# In-Out.net
KiCad netlist of a schematic drawn in Altium Designer
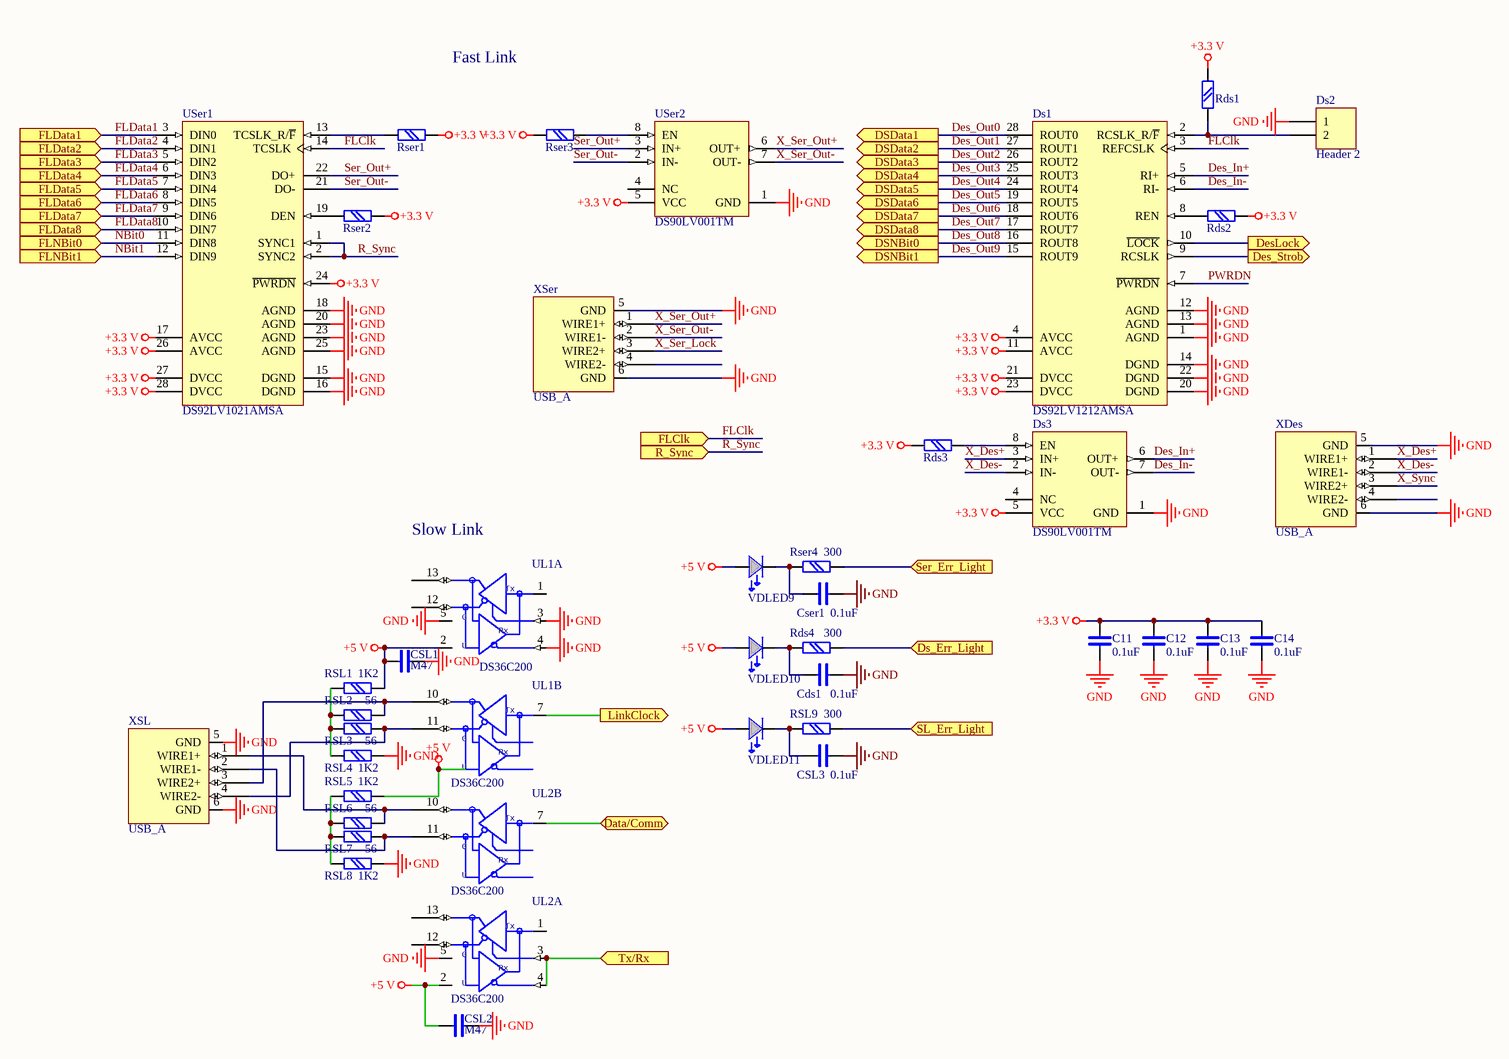
[diagram p0: In-Out.SchDoc]

(export (version "E")
  (design (tool "Eeschema 10.0.6"))
  (components
    (comp (ref "C11") (value "0.1uF") (footprint "chip0805") (libsource (lib "*") (part "C")))
    (comp (ref "C12") (value "0.1uF") (footprint "chip0805") (libsource (lib "*") (part "C")))
    (comp (ref "C13") (value "0.1uF") (footprint "chip0805") (libsource (lib "*") (part "C")))
    (comp (ref "C14") (value "0.1uF") (footprint "chip0805") (libsource (lib "*") (part "C")))
    (comp (ref "Cds1") (value "0.1uF") (footprint "chip0805") (libsource (lib "vDevice") (part "C")))
    (comp (ref "Cser1") (value "0.1uF") (footprint "chip0805") (libsource (lib "vDevice") (part "C")))
    (comp (ref "CSL1") (value "M47") (footprint "chip0805") (libsource (lib "*") (part "C")))
    (comp (ref "CSL2") (value "M47") (footprint "chip0805") (libsource (lib "*") (part "C")))
    (comp (ref "CSL3") (value "0.1uF") (footprint "chip0805") (libsource (lib "vDevice") (part "C")))
    (comp (ref "Ds1")
      (value "DS92LV1212AMSA")
      (footprint "MSA28_N")
      (fields
        (field (name "MANUFACTURER") "National Semiconductor")
        (field (name "PUBLISHER") "Altium Limited")
      )
      (libsource (lib "NSC Interface") (part "DS92LV1212AMSA"))
    )
    (comp (ref "Ds2")
      (value "Header 2")
      (footprint "HDR1X2")
      (description "Header, 2-Pin")
      (fields (field (name "PUBLISHER") "Altium Limited"))
      (libsource (lib "Miscellaneous Connectors") (part "Header 2"))
    )
    (comp (ref "Ds3")
      (value "DS90LV001TM")
      (footprint "M08A_N")
      (description "800 Mbps LVDS Buffer, 8-pin Narrow SOIC")
      (fields
        (field (name "MANUFACTURER") "National Semiconductor")
        (field (name "PUBLISHER") "Altium Limited")
      )
      (libsource (lib "NSC Interface") (part "DS90LV001TM"))
    )
    (comp (ref "Rds1") (value "R") (footprint "chip0805") (libsource (lib "vDevice") (part "R")))
    (comp (ref "Rds2") (value "R") (footprint "chip0805") (libsource (lib "vDevice") (part "R")))
    (comp (ref "Rds3") (value "R") (footprint "chip0805") (libsource (lib "vDevice") (part "R")))
    (comp (ref "Rds4") (value "300") (footprint "chip0805") (libsource (lib "vDevice") (part "R")))
    (comp (ref "Rser1") (value "R") (footprint "chip0805") (libsource (lib "vDevice") (part "R")))
    (comp (ref "Rser2") (value "R") (footprint "chip0805") (libsource (lib "vDevice") (part "R")))
    (comp (ref "Rser3") (value "R") (footprint "chip0805") (libsource (lib "vDevice") (part "R")))
    (comp (ref "Rser4") (value "300") (footprint "chip0805") (libsource (lib "vDevice") (part "R")))
    (comp (ref "RSL1") (value "1K2") (footprint "chip0805") (libsource (lib "*") (part "R")))
    (comp (ref "RSL2") (value "56") (footprint "chip0805") (libsource (lib "*") (part "R")))
    (comp (ref "RSL3") (value "56") (footprint "chip0805") (libsource (lib "*") (part "R")))
    (comp (ref "RSL4") (value "1K2") (footprint "chip0805") (libsource (lib "*") (part "R")))
    (comp (ref "RSL5") (value "1K2") (footprint "chip0805") (libsource (lib "*") (part "R")))
    (comp (ref "RSL6") (value "56") (footprint "chip0805") (libsource (lib "*") (part "R")))
    (comp (ref "RSL7") (value "56") (footprint "chip0805") (libsource (lib "*") (part "R")))
    (comp (ref "RSL8") (value "1K2") (footprint "chip0805") (libsource (lib "*") (part "R")))
    (comp (ref "RSL9") (value "300") (footprint "chip0805") (libsource (lib "vDevice") (part "R")))
    (comp (ref "UL1") (value "DS36C200") (footprint "M14A_N") (libsource (lib "*") (part "DS36C200")))
    (comp (ref "UL2") (value "DS36C200") (footprint "M14A_N") (libsource (lib "*") (part "DS36C200")))
    (comp (ref "USer1")
      (value "DS92LV1021AMSA")
      (footprint "MSA28_N")
      (description "16 MHz - 40 MHz 10-Bit Serializer, 28-pin SSOP-EIAJ")
      (fields
        (field (name "MANUFACTURER") "National Semiconductor")
        (field (name "PUBLISHER") "Altium Limited")
      )
      (libsource (lib "NSC Interface") (part "DS92LV1021AMSA"))
    )
    (comp (ref "USer2")
      (value "DS90LV001TM")
      (footprint "M08A_N")
      (description "800 Mbps LVDS Buffer, 8-pin Narrow SOIC")
      (fields
        (field (name "MANUFACTURER") "National Semiconductor")
        (field (name "PUBLISHER") "Altium Limited")
      )
      (libsource (lib "NSC Interface") (part "DS90LV001TM"))
    )
    (comp (ref "VDLED9") (value "LED") (footprint "LED2P5_H") (libsource (lib "*") (part "AL307")))
    (comp (ref "VDLED10") (value "LED") (footprint "LED2P5_H") (libsource (lib "*") (part "AL307")))
    (comp (ref "VDLED11") (value "LED") (footprint "LED2P5_H") (libsource (lib "*") (part "AL307")))
    (comp (ref "XDes") (value "USB_A") (footprint "USB2.5-2H4B") (libsource (lib "Con USB") (part "USB_A")))
    (comp (ref "XSer") (value "USB_A") (footprint "USB2.5-2H4B") (libsource (lib "Con USB") (part "USB_A")))
    (comp (ref "XSL") (value "USB_A") (footprint "USB2.5-2H4B") (libsource (lib "Con USB") (part "USB_A")))
  )
  (nets
    (net (code "1") (name "+3.3 V") (class "Default")
      (node (ref "C11") (pin "2") (pinfunction "2_2") (pintype "passive"))
      (node (ref "C12") (pin "2") (pinfunction "2_2") (pintype "passive"))
      (node (ref "C13") (pin "2") (pinfunction "2_2") (pintype "passive"))
      (node (ref "C14") (pin "2") (pinfunction "2_2") (pintype "passive"))
      (node (ref "Ds1") (pin "11") (pinfunction "AVCC_11") (pintype "power_in"))
      (node (ref "Ds1") (pin "21") (pinfunction "DVCC_21") (pintype "power_in"))
      (node (ref "Ds1") (pin "23") (pinfunction "DVCC_23") (pintype "power_in"))
      (node (ref "Ds1") (pin "4") (pinfunction "AVCC_4") (pintype "power_in"))
      (node (ref "Ds3") (pin "5") (pinfunction "VCC_5") (pintype "power_in"))
      (node (ref "Rds1") (pin "1") (pinfunction "1_1") (pintype "passive"))
      (node (ref "Rds2") (pin "2") (pinfunction "2_2") (pintype "passive"))
      (node (ref "Rds3") (pin "2") (pinfunction "2_2") (pintype "passive"))
      (node (ref "Rser1") (pin "1") (pinfunction "1_1") (pintype "passive"))
      (node (ref "Rser2") (pin "2") (pinfunction "2_2") (pintype "passive"))
      (node (ref "Rser3") (pin "2") (pinfunction "2_2") (pintype "passive"))
      (node (ref "USer1") (pin "17") (pinfunction "AVCC_17") (pintype "power_in"))
      (node (ref "USer1") (pin "24") (pinfunction "~{PWRDN}_24") (pintype "input"))
      (node (ref "USer1") (pin "26") (pinfunction "AVCC_26") (pintype "power_in"))
      (node (ref "USer1") (pin "27") (pinfunction "DVCC_27") (pintype "power_in"))
      (node (ref "USer1") (pin "28") (pinfunction "DVCC_28") (pintype "power_in"))
      (node (ref "USer2") (pin "5") (pinfunction "VCC_5") (pintype "power_in"))
    )
    (net (code "2") (name "+5 V") (class "Default")
      (node (ref "CSL1") (pin "1") (pinfunction "1_1") (pintype "passive"))
      (node (ref "CSL2") (pin "1") (pinfunction "1_1") (pintype "passive"))
      (node (ref "RSL1") (pin "2") (pinfunction "2_2") (pintype "passive"))
      (node (ref "RSL5") (pin "2") (pinfunction "2_2") (pintype "passive"))
      (node (ref "UL1") (pin "2") (pinfunction "VCC_2") (pintype "passive"))
      (node (ref "UL2") (pin "2") (pinfunction "VCC_2") (pintype "passive"))
      (node (ref "VDLED10") (pin "ANOD") (pinfunction "ANOD_ANOD") (pintype "passive"))
      (node (ref "VDLED11") (pin "ANOD") (pinfunction "ANOD_ANOD") (pintype "passive"))
      (node (ref "VDLED9") (pin "ANOD") (pinfunction "ANOD_ANOD") (pintype "passive"))
    )
    (net (code "3") (name "/Data{slash}Comm") (class "Default")
      (node (ref "UL2") (pin "7") (pinfunction "DATA_7") (pintype "bidirectional"))
    )
    (net (code "4") (name "/DesLock") (class "Default")
      (node (ref "Ds1") (pin "10") (pinfunction "~{LOCK}_10") (pintype "output"))
    )
    (net (code "5") (name "/Des_In+") (class "Default")
      (node (ref "Ds1") (pin "5") (pinfunction "RI+_5") (pintype "input"))
      (node (ref "Ds3") (pin "6") (pinfunction "OUT+_6") (pintype "output"))
    )
    (net (code "6") (name "/Des_In-") (class "Default")
      (node (ref "Ds1") (pin "6") (pinfunction "RI-_6") (pintype "input"))
      (node (ref "Ds3") (pin "7") (pinfunction "OUT-_7") (pintype "output"))
    )
    (net (code "7") (name "/Des_Out0") (class "Default")
      (node (ref "Ds1") (pin "28") (pinfunction "ROUT0_28") (pintype "tri_state"))
    )
    (net (code "8") (name "/Des_Out1") (class "Default")
      (node (ref "Ds1") (pin "27") (pinfunction "ROUT1_27") (pintype "tri_state"))
    )
    (net (code "9") (name "/Des_Out2") (class "Default")
      (node (ref "Ds1") (pin "26") (pinfunction "ROUT2_26") (pintype "tri_state"))
    )
    (net (code "10") (name "/Des_Out3") (class "Default")
      (node (ref "Ds1") (pin "25") (pinfunction "ROUT3_25") (pintype "tri_state"))
    )
    (net (code "11") (name "/Des_Out4") (class "Default")
      (node (ref "Ds1") (pin "24") (pinfunction "ROUT4_24") (pintype "tri_state"))
    )
    (net (code "12") (name "/Des_Out5") (class "Default")
      (node (ref "Ds1") (pin "19") (pinfunction "ROUT5_19") (pintype "tri_state"))
    )
    (net (code "13") (name "/Des_Out6") (class "Default")
      (node (ref "Ds1") (pin "18") (pinfunction "ROUT6_18") (pintype "tri_state"))
    )
    (net (code "14") (name "/Des_Out7") (class "Default")
      (node (ref "Ds1") (pin "17") (pinfunction "ROUT7_17") (pintype "tri_state"))
    )
    (net (code "15") (name "/Des_Out8") (class "Default")
      (node (ref "Ds1") (pin "16") (pinfunction "ROUT8_16") (pintype "tri_state"))
    )
    (net (code "16") (name "/Des_Out9") (class "Default")
      (node (ref "Ds1") (pin "15") (pinfunction "ROUT9_15") (pintype "tri_state"))
    )
    (net (code "17") (name "/Des_Strob") (class "Default")
      (node (ref "Ds1") (pin "9") (pinfunction "RCSLK_9") (pintype "output"))
    )
    (net (code "18") (name "/Ds_Err_Light") (class "Default")
      (node (ref "Rds4") (pin "1") (pinfunction "1_1") (pintype "passive"))
    )
    (net (code "19") (name "/FLClk") (class "Default")
      (node (ref "Ds1") (pin "3") (pinfunction "REFCSLK_3") (pintype "input"))
      (node (ref "USer1") (pin "14") (pinfunction "TCSLK_14") (pintype "input"))
    )
    (net (code "20") (name "/FLData1") (class "Default")
      (node (ref "USer1") (pin "3") (pinfunction "DIN0_3") (pintype "input"))
    )
    (net (code "21") (name "/FLData2") (class "Default")
      (node (ref "USer1") (pin "4") (pinfunction "DIN1_4") (pintype "input"))
    )
    (net (code "22") (name "/FLData3") (class "Default")
      (node (ref "USer1") (pin "5") (pinfunction "DIN2_5") (pintype "input"))
    )
    (net (code "23") (name "/FLData4") (class "Default")
      (node (ref "USer1") (pin "6") (pinfunction "DIN3_6") (pintype "input"))
    )
    (net (code "24") (name "/FLData5") (class "Default")
      (node (ref "USer1") (pin "7") (pinfunction "DIN4_7") (pintype "input"))
    )
    (net (code "25") (name "/FLData6") (class "Default")
      (node (ref "USer1") (pin "8") (pinfunction "DIN5_8") (pintype "input"))
    )
    (net (code "26") (name "/FLData7") (class "Default")
      (node (ref "USer1") (pin "9") (pinfunction "DIN6_9") (pintype "input"))
    )
    (net (code "27") (name "/FLData8") (class "Default")
      (node (ref "USer1") (pin "10") (pinfunction "DIN7_10") (pintype "input"))
    )
    (net (code "28") (name "/LinkClock") (class "Default")
      (node (ref "UL1") (pin "7") (pinfunction "DATA_7") (pintype "bidirectional"))
    )
    (net (code "29") (name "/NBit0") (class "Default")
      (node (ref "USer1") (pin "11") (pinfunction "DIN8_11") (pintype "input"))
    )
    (net (code "30") (name "/NBit1") (class "Default")
      (node (ref "USer1") (pin "12") (pinfunction "DIN9_12") (pintype "input"))
    )
    (net (code "31") (name "/PWRDN") (class "Default")
      (node (ref "Ds1") (pin "7") (pinfunction "~{PWRDN}_7") (pintype "input"))
    )
    (net (code "32") (name "/R_Sync") (class "Default")
      (node (ref "USer1") (pin "1") (pinfunction "SYNC1_1") (pintype "input"))
      (node (ref "USer1") (pin "2") (pinfunction "SYNC2_2") (pintype "input"))
    )
    (net (code "33") (name "/SL_Err_Light") (class "Default")
      (node (ref "RSL9") (pin "1") (pinfunction "1_1") (pintype "passive"))
    )
    (net (code "34") (name "/Ser_Err_Light") (class "Default")
      (node (ref "Rser4") (pin "1") (pinfunction "1_1") (pintype "passive"))
    )
    (net (code "35") (name "/Ser_Out+") (class "Default")
      (node (ref "USer1") (pin "22") (pinfunction "DO+_22") (pintype "tri_state"))
      (node (ref "USer2") (pin "3") (pinfunction "IN+_3") (pintype "input"))
    )
    (net (code "36") (name "/Ser_Out-") (class "Default")
      (node (ref "USer1") (pin "21") (pinfunction "DO-_21") (pintype "tri_state"))
      (node (ref "USer2") (pin "2") (pinfunction "IN-_2") (pintype "input"))
    )
    (net (code "37") (name "/Tx{slash}Rx") (class "Default")
      (node (ref "UL2") (pin "3") (pinfunction "TE_3") (pintype "input"))
      (node (ref "UL2") (pin "4") (pinfunction "RE_4") (pintype "input"))
    )
    (net (code "38") (name "/X_Des+") (class "Default")
      (node (ref "Ds3") (pin "3") (pinfunction "IN+_3") (pintype "input"))
      (node (ref "XDes") (pin "1") (pinfunction "WIRE1+_1") (pintype "bidirectional"))
    )
    (net (code "39") (name "/X_Des-") (class "Default")
      (node (ref "Ds3") (pin "2") (pinfunction "IN-_2") (pintype "input"))
      (node (ref "XDes") (pin "2") (pinfunction "WIRE1-_2") (pintype "bidirectional"))
    )
    (net (code "40") (name "/X_Ser_Lock") (class "Default")
      (node (ref "XSer") (pin "3") (pinfunction "WIRE2+_3") (pintype "bidirectional"))
    )
    (net (code "41") (name "/X_Ser_Out+") (class "Default")
      (node (ref "USer2") (pin "6") (pinfunction "OUT+_6") (pintype "output"))
      (node (ref "XSer") (pin "1") (pinfunction "WIRE1+_1") (pintype "bidirectional"))
    )
    (net (code "42") (name "/X_Ser_Out-") (class "Default")
      (node (ref "USer2") (pin "7") (pinfunction "OUT-_7") (pintype "output"))
      (node (ref "XSer") (pin "2") (pinfunction "WIRE1-_2") (pintype "bidirectional"))
    )
    (net (code "43") (name "/X_Sync") (class "Default")
      (node (ref "XDes") (pin "3") (pinfunction "WIRE2+_3") (pintype "bidirectional"))
    )
    (net (code "44") (name "GND") (class "Default")
      (node (ref "C11") (pin "1") (pinfunction "1_1") (pintype "passive"))
      (node (ref "C12") (pin "1") (pinfunction "1_1") (pintype "passive"))
      (node (ref "C13") (pin "1") (pinfunction "1_1") (pintype "passive"))
      (node (ref "C14") (pin "1") (pinfunction "1_1") (pintype "passive"))
      (node (ref "CSL1") (pin "2") (pinfunction "2_2") (pintype "passive"))
      (node (ref "CSL2") (pin "2") (pinfunction "2_2") (pintype "passive"))
      (node (ref "CSL3") (pin "2") (pinfunction "2_2") (pintype "passive"))
      (node (ref "Cds1") (pin "2") (pinfunction "2_2") (pintype "passive"))
      (node (ref "Cser1") (pin "2") (pinfunction "2_2") (pintype "passive"))
      (node (ref "Ds1") (pin "1") (pinfunction "AGND_1") (pintype "power_in"))
      (node (ref "Ds1") (pin "12") (pinfunction "AGND_12") (pintype "power_in"))
      (node (ref "Ds1") (pin "13") (pinfunction "AGND_13") (pintype "power_in"))
      (node (ref "Ds1") (pin "14") (pinfunction "DGND_14") (pintype "power_in"))
      (node (ref "Ds1") (pin "20") (pinfunction "DGND_20") (pintype "power_in"))
      (node (ref "Ds1") (pin "22") (pinfunction "DGND_22") (pintype "power_in"))
      (node (ref "Ds2") (pin "1") (pinfunction "1_1") (pintype "passive"))
      (node (ref "Ds3") (pin "1") (pinfunction "GND_1") (pintype "power_in"))
      (node (ref "RSL4") (pin "2") (pinfunction "2_2") (pintype "passive"))
      (node (ref "RSL8") (pin "2") (pinfunction "2_2") (pintype "passive"))
      (node (ref "UL1") (pin "3") (pinfunction "TE_3") (pintype "input"))
      (node (ref "UL1") (pin "4") (pinfunction "RE_4") (pintype "input"))
      (node (ref "UL1") (pin "5") (pinfunction "GND_5") (pintype "passive"))
      (node (ref "UL2") (pin "5") (pinfunction "GND_5") (pintype "passive"))
      (node (ref "USer1") (pin "15") (pinfunction "DGND_15") (pintype "power_in"))
      (node (ref "USer1") (pin "16") (pinfunction "DGND_16") (pintype "power_in"))
      (node (ref "USer1") (pin "18") (pinfunction "AGND_18") (pintype "power_in"))
      (node (ref "USer1") (pin "20") (pinfunction "AGND_20") (pintype "power_in"))
      (node (ref "USer1") (pin "23") (pinfunction "AGND_23") (pintype "power_in"))
      (node (ref "USer1") (pin "25") (pinfunction "AGND_25") (pintype "power_in"))
      (node (ref "USer2") (pin "1") (pinfunction "GND_1") (pintype "power_in"))
      (node (ref "XDes") (pin "5") (pinfunction "GND_5") (pintype "passive"))
      (node (ref "XDes") (pin "6") (pinfunction "GND_6") (pintype "passive"))
      (node (ref "XSL") (pin "5") (pinfunction "GND_5") (pintype "passive"))
      (node (ref "XSL") (pin "6") (pinfunction "GND_6") (pintype "passive"))
      (node (ref "XSer") (pin "5") (pinfunction "GND_5") (pintype "passive"))
      (node (ref "XSer") (pin "6") (pinfunction "GND_6") (pintype "passive"))
    )
    (net (code "45") (name "Net-(CSL3-Pad1)") (class "Default")
      (node (ref "CSL3") (pin "1") (pinfunction "1_1") (pintype "passive"))
      (node (ref "RSL9") (pin "2") (pinfunction "2_2") (pintype "passive"))
      (node (ref "VDLED11") (pin "CATH") (pinfunction "CATH_CATH") (pintype "passive"))
    )
    (net (code "46") (name "Net-(Cds1-Pad1)") (class "Default")
      (node (ref "Cds1") (pin "1") (pinfunction "1_1") (pintype "passive"))
      (node (ref "Rds4") (pin "2") (pinfunction "2_2") (pintype "passive"))
      (node (ref "VDLED10") (pin "CATH") (pinfunction "CATH_CATH") (pintype "passive"))
    )
    (net (code "47") (name "Net-(Cser1-Pad1)") (class "Default")
      (node (ref "Cser1") (pin "1") (pinfunction "1_1") (pintype "passive"))
      (node (ref "Rser4") (pin "2") (pinfunction "2_2") (pintype "passive"))
      (node (ref "VDLED9") (pin "CATH") (pinfunction "CATH_CATH") (pintype "passive"))
    )
    (net (code "48") (name "Net-(Ds1-RCSLK_R{slash}~{F})") (class "Default")
      (node (ref "Ds1") (pin "2") (pinfunction "RCSLK_R/~{F}_2") (pintype "input"))
      (node (ref "Ds2") (pin "2") (pinfunction "2_2") (pintype "passive"))
      (node (ref "Rds1") (pin "2") (pinfunction "2_2") (pintype "passive"))
    )
    (net (code "49") (name "Net-(Ds1-REN)") (class "Default")
      (node (ref "Ds1") (pin "8") (pinfunction "REN_8") (pintype "input"))
      (node (ref "Rds2") (pin "1") (pinfunction "1_1") (pintype "passive"))
    )
    (net (code "50") (name "Net-(Ds3-EN)") (class "Default")
      (node (ref "Ds3") (pin "8") (pinfunction "EN_8") (pintype "input"))
      (node (ref "Rds3") (pin "1") (pinfunction "1_1") (pintype "passive"))
    )
    (net (code "51") (name "Net-(RSL1-Pad1)") (class "Default")
      (node (ref "RSL1") (pin "1") (pinfunction "1_1") (pintype "passive"))
      (node (ref "RSL2") (pin "1") (pinfunction "1_1") (pintype "passive"))
      (node (ref "RSL3") (pin "1") (pinfunction "1_1") (pintype "passive"))
      (node (ref "RSL4") (pin "1") (pinfunction "1_1") (pintype "passive"))
    )
    (net (code "52") (name "Net-(RSL5-Pad1)") (class "Default")
      (node (ref "RSL5") (pin "1") (pinfunction "1_1") (pintype "passive"))
      (node (ref "RSL6") (pin "1") (pinfunction "1_1") (pintype "passive"))
      (node (ref "RSL7") (pin "1") (pinfunction "1_1") (pintype "passive"))
      (node (ref "RSL8") (pin "1") (pinfunction "1_1") (pintype "passive"))
    )
    (net (code "53") (name "Net-(UL1B-WIRE+)") (class "Default")
      (node (ref "RSL2") (pin "2") (pinfunction "2_2") (pintype "passive"))
      (node (ref "UL1") (pin "10") (pinfunction "WIRE+_10") (pintype "bidirectional"))
      (node (ref "XSL") (pin "3") (pinfunction "WIRE2+_3") (pintype "bidirectional"))
    )
    (net (code "54") (name "Net-(UL1B-WIRE-)") (class "Default")
      (node (ref "RSL3") (pin "2") (pinfunction "2_2") (pintype "passive"))
      (node (ref "UL1") (pin "11") (pinfunction "WIRE-_11") (pintype "bidirectional"))
      (node (ref "XSL") (pin "4") (pinfunction "WIRE2-_4") (pintype "bidirectional"))
    )
    (net (code "55") (name "Net-(UL2B-WIRE+)") (class "Default")
      (node (ref "RSL6") (pin "2") (pinfunction "2_2") (pintype "passive"))
      (node (ref "UL2") (pin "10") (pinfunction "WIRE+_10") (pintype "bidirectional"))
      (node (ref "XSL") (pin "1") (pinfunction "WIRE1+_1") (pintype "bidirectional"))
    )
    (net (code "56") (name "Net-(UL2B-WIRE-)") (class "Default")
      (node (ref "RSL7") (pin "2") (pinfunction "2_2") (pintype "passive"))
      (node (ref "UL2") (pin "11") (pinfunction "WIRE-_11") (pintype "bidirectional"))
      (node (ref "XSL") (pin "2") (pinfunction "WIRE1-_2") (pintype "bidirectional"))
    )
    (net (code "57") (name "Net-(USer1-DEN)") (class "Default")
      (node (ref "Rser2") (pin "1") (pinfunction "1_1") (pintype "passive"))
      (node (ref "USer1") (pin "19") (pinfunction "DEN_19") (pintype "input"))
    )
    (net (code "58") (name "Net-(USer1-TCSLK_R{slash}~{F})") (class "Default")
      (node (ref "Rser1") (pin "2") (pinfunction "2_2") (pintype "passive"))
      (node (ref "USer1") (pin "13") (pinfunction "TCSLK_R/~{F}_13") (pintype "input"))
    )
    (net (code "59") (name "Net-(USer2-EN)") (class "Default")
      (node (ref "Rser3") (pin "1") (pinfunction "1_1") (pintype "passive"))
      (node (ref "USer2") (pin "8") (pinfunction "EN_8") (pintype "input"))
    )
    (net (code "60") (name "unconnected-(Ds3-NC-Pad4)") (class "Default")
      (node (ref "Ds3") (pin "4") (pinfunction "NC_4") (pintype "passive"))
    )
    (net (code "61") (name "unconnected-(UL1A-DATA-Pad1)") (class "Default")
      (node (ref "UL1") (pin "1") (pinfunction "DATA_1") (pintype "bidirectional"))
    )
    (net (code "62") (name "unconnected-(UL1A-WIRE+-Pad13)") (class "Default")
      (node (ref "UL1") (pin "13") (pinfunction "WIRE+_13") (pintype "bidirectional"))
    )
    (net (code "63") (name "unconnected-(UL1A-WIRE--Pad12)") (class "Default")
      (node (ref "UL1") (pin "12") (pinfunction "WIRE-_12") (pintype "bidirectional"))
    )
    (net (code "64") (name "unconnected-(UL2A-DATA-Pad1)") (class "Default")
      (node (ref "UL2") (pin "1") (pinfunction "DATA_1") (pintype "bidirectional"))
    )
    (net (code "65") (name "unconnected-(UL2A-WIRE+-Pad13)") (class "Default")
      (node (ref "UL2") (pin "13") (pinfunction "WIRE+_13") (pintype "bidirectional"))
    )
    (net (code "66") (name "unconnected-(UL2A-WIRE--Pad12)") (class "Default")
      (node (ref "UL2") (pin "12") (pinfunction "WIRE-_12") (pintype "bidirectional"))
    )
    (net (code "67") (name "unconnected-(USer2-NC-Pad4)") (class "Default")
      (node (ref "USer2") (pin "4") (pinfunction "NC_4") (pintype "passive"))
    )
    (net (code "68") (name "unconnected-(XDes-WIRE2--Pad4)") (class "Default")
      (node (ref "XDes") (pin "4") (pinfunction "WIRE2-_4") (pintype "bidirectional"))
    )
    (net (code "69") (name "unconnected-(XSer-WIRE2--Pad4)") (class "Default")
      (node (ref "XSer") (pin "4") (pinfunction "WIRE2-_4") (pintype "bidirectional"))
    )
  )
)
